# thegardening2_1.net
KiCad netlist of a schematic drawn in EAGLE
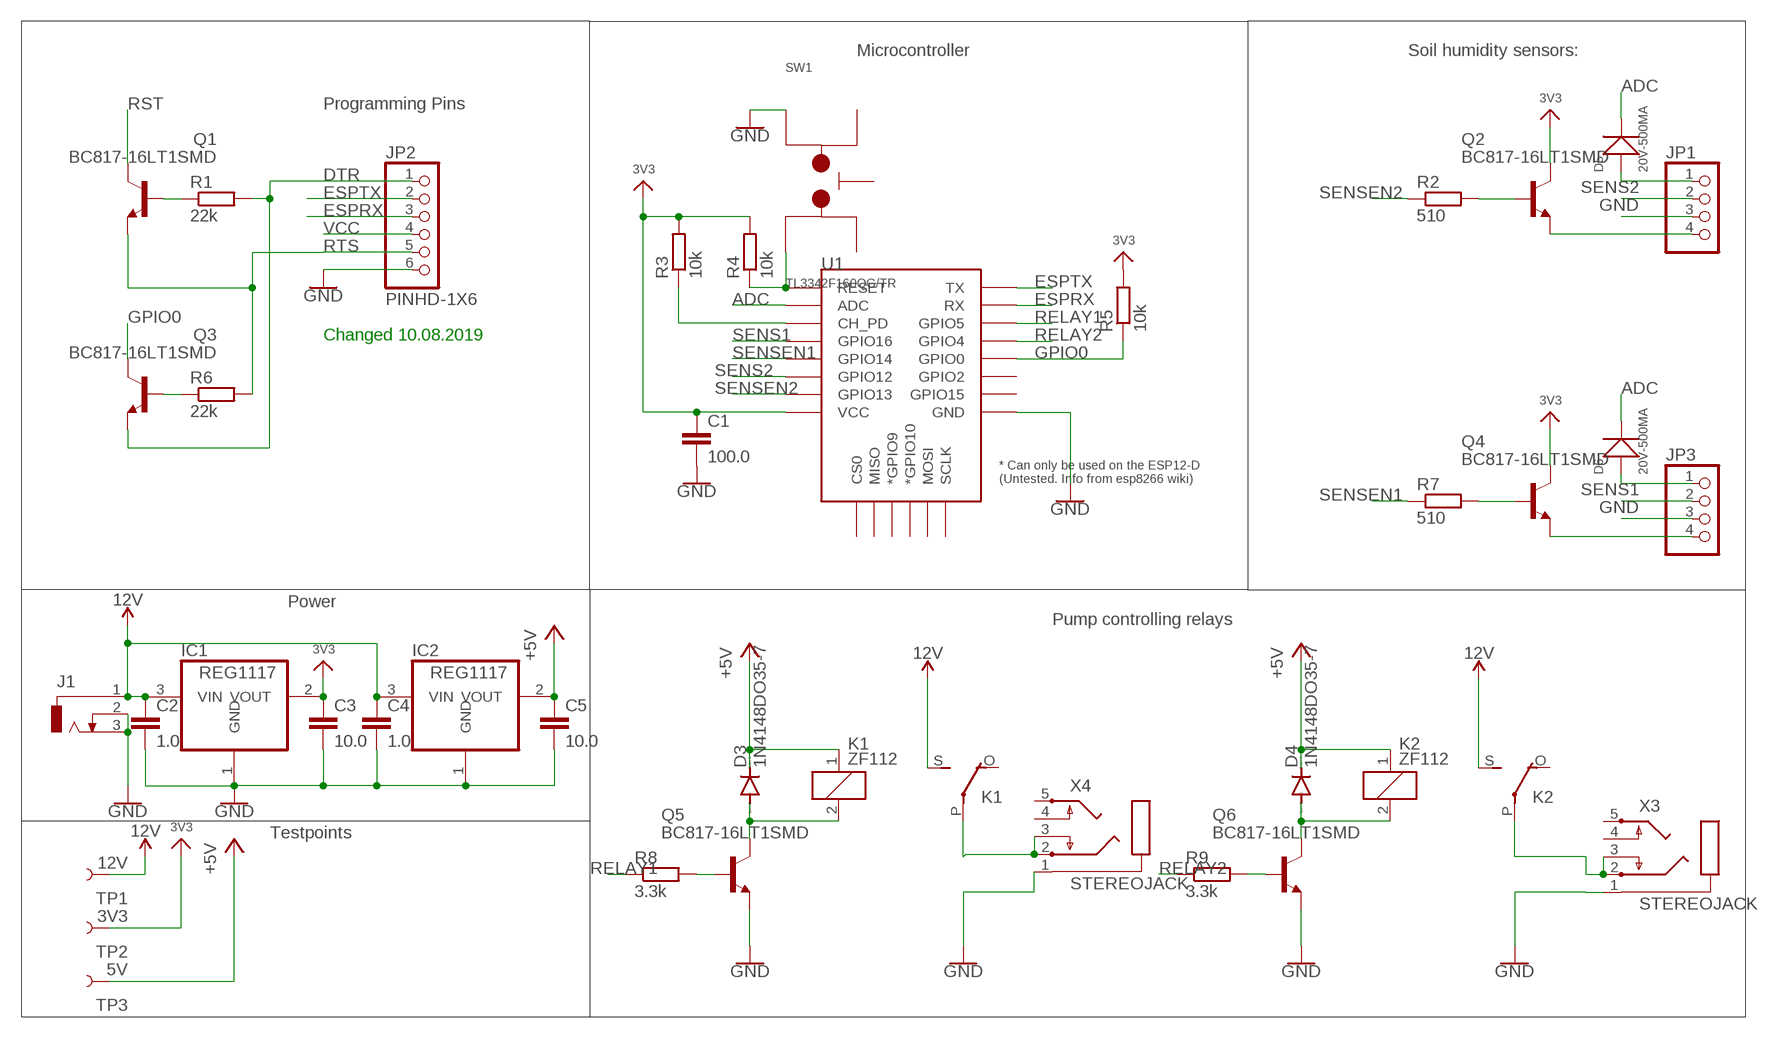
[diagram p0: schematic, sheet 1]

(export (version "E")
  (design (tool "Eeschema 10.0.6"))
  (components
    (comp (ref "C1")
      (value "100.0")
      (footprint "eagle-import:C0805")
      (libsource (lib "eagle-import") (part "C-EUC0805"))
    )
    (comp (ref "C2")
      (value "1.0")
      (footprint "eagle-import:C0805")
      (libsource (lib "eagle-import") (part "C-EUC0805"))
    )
    (comp (ref "C3")
      (value "10.0")
      (footprint "eagle-import:C0805")
      (libsource (lib "eagle-import") (part "C-EUC0805"))
    )
    (comp (ref "C4")
      (value "1.0")
      (footprint "eagle-import:C0805")
      (libsource (lib "eagle-import") (part "C-EUC0805"))
    )
    (comp (ref "C5")
      (value "10.0")
      (footprint "eagle-import:C0805")
      (libsource (lib "eagle-import") (part "C-EUC0805"))
    )
    (comp (ref "D3")
      (value "1N4148DO35-7")
      (footprint "eagle-import:DO35-7")
      (libsource (lib "eagle-import") (part "1N4148DO35-7"))
    )
    (comp (ref "D4")
      (value "1N4148DO35-7")
      (footprint "eagle-import:DO35-7")
      (libsource (lib "eagle-import") (part "1N4148DO35-7"))
    )
    (comp (ref "D5")
      (value "20V-500MA")
      (footprint "eagle-import:SOD-123")
      (fields (field (name "MPN") "SS0520-7-F"))
      (libsource (lib "eagle-import") (part "SMD-DIODE-SCHOTTKY-20V-500MA(SOD-123)"))
    )
    (comp (ref "D6")
      (value "20V-500MA")
      (footprint "eagle-import:SOD-123")
      (fields (field (name "MPN") "SS0520-7-F"))
      (libsource (lib "eagle-import") (part "SMD-DIODE-SCHOTTKY-20V-500MA(SOD-123)"))
    )
    (comp (ref "IC1")
      (value "REG1117")
      (footprint "eagle-import:SOT223")
      (libsource (lib "eagle-import") (part "REG1117"))
    )
    (comp (ref "IC2")
      (value "REG1117")
      (footprint "eagle-import:SOT223")
      (libsource (lib "eagle-import") (part "REG1117"))
    )
    (comp (ref "J1")
      (value "DCJ0303")
      (footprint "eagle-import:DCJ0303")
      (libsource (lib "eagle-import") (part "DCJ0303"))
    )
    (comp (ref "JP1")
      (value "PINHD-1X4")
      (footprint "eagle-import:1X04")
      (libsource (lib "eagle-import") (part "PINHD-1X4"))
    )
    (comp (ref "JP2")
      (value "PINHD-1X6")
      (footprint "eagle-import:1X06")
      (libsource (lib "eagle-import") (part "PINHD-1X6"))
    )
    (comp (ref "JP3")
      (value "PINHD-1X4")
      (footprint "eagle-import:1X04")
      (libsource (lib "eagle-import") (part "PINHD-1X4"))
    )
    (comp (ref "K1")
      (value "ZF112")
      (footprint "eagle-import:ZF112")
      (libsource (lib "eagle-import") (part "ZF112"))
    )
    (comp (ref "K2")
      (value "ZF112")
      (footprint "eagle-import:ZF112")
      (libsource (lib "eagle-import") (part "ZF112"))
    )
    (comp (ref "Q1")
      (value "BC817-16LT1SMD")
      (footprint "eagle-import:SOT23-BEC")
      (libsource (lib "eagle-import") (part "BC817SMD-16LT1"))
    )
    (comp (ref "Q2")
      (value "BC817-16LT1SMD")
      (footprint "eagle-import:SOT23-BEC")
      (libsource (lib "eagle-import") (part "BC817SMD-16LT1"))
    )
    (comp (ref "Q3")
      (value "BC817-16LT1SMD")
      (footprint "eagle-import:SOT23-BEC")
      (libsource (lib "eagle-import") (part "BC817SMD-16LT1"))
    )
    (comp (ref "Q4")
      (value "BC817-16LT1SMD")
      (footprint "eagle-import:SOT23-BEC")
      (libsource (lib "eagle-import") (part "BC817SMD-16LT1"))
    )
    (comp (ref "Q5")
      (value "BC817-16LT1SMD")
      (footprint "eagle-import:SOT23-BEC")
      (libsource (lib "eagle-import") (part "BC817SMD-16LT1"))
    )
    (comp (ref "Q6")
      (value "BC817-16LT1SMD")
      (footprint "eagle-import:SOT23-BEC")
      (libsource (lib "eagle-import") (part "BC817SMD-16LT1"))
    )
    (comp (ref "R1")
      (value "22k")
      (footprint "eagle-import:R0805")
      (libsource (lib "eagle-import") (part "R-EU_R0805"))
    )
    (comp (ref "R2")
      (value "510")
      (footprint "eagle-import:R0805")
      (libsource (lib "eagle-import") (part "R-EU_R0805"))
    )
    (comp (ref "R3")
      (value "10k")
      (footprint "eagle-import:R0805")
      (libsource (lib "eagle-import") (part "R-EU_R0805"))
    )
    (comp (ref "R4")
      (value "10k")
      (footprint "eagle-import:R0805")
      (libsource (lib "eagle-import") (part "R-EU_R0805"))
    )
    (comp (ref "R5")
      (value "10k")
      (footprint "eagle-import:R0805")
      (libsource (lib "eagle-import") (part "R-EU_R0805"))
    )
    (comp (ref "R6")
      (value "22k")
      (footprint "eagle-import:R0805")
      (libsource (lib "eagle-import") (part "R-EU_R0805"))
    )
    (comp (ref "R7")
      (value "510")
      (footprint "eagle-import:R0805")
      (libsource (lib "eagle-import") (part "R-EU_R0805"))
    )
    (comp (ref "R8")
      (value "3.3k")
      (footprint "eagle-import:R0805")
      (libsource (lib "eagle-import") (part "R-EU_R0805"))
    )
    (comp (ref "R9")
      (value "3.3k")
      (footprint "eagle-import:R0805")
      (libsource (lib "eagle-import") (part "R-EU_R0805"))
    )
    (comp (ref "SW1")
      (value "TL3342F160QG/TR")
      (footprint "eagle-import:TL3342F160QG_TR")
      (fields
        (field (name "DIGI_KEY_PART_NUMBER") "EG2531CT-ND")
        (field (name "MANUFACTURER") "E-Switch")
        (field (name "CREATED_BY") "PCBLayout.com")
      )
      (libsource (lib "eagle-import") (part "TL3342F160QG/TR"))
    )
    (comp (ref "TP1")
      (value "12V")
      (footprint "eagle-import:TP_15TH")
      (libsource (lib "eagle-import") (part "TEST-POINTTP_15TH_THRU"))
    )
    (comp (ref "TP2")
      (value "3V3")
      (footprint "eagle-import:TP_15TH")
      (libsource (lib "eagle-import") (part "TEST-POINTTP_15TH_THRU"))
    )
    (comp (ref "TP3")
      (value "5V")
      (footprint "eagle-import:TP_15TH")
      (libsource (lib "eagle-import") (part "TEST-POINTTP_15TH_THRU"))
    )
    (comp (ref "U1")
      (value "ESP12ESMD")
      (footprint "eagle-import:ESP12E-SMD")
      (libsource (lib "eagle-import") (part "ESP12ESMD"))
    )
    (comp (ref "X3")
      (value "STEREOJACK")
      (footprint "eagle-import:STX3100")
      (libsource (lib "eagle-import") (part "STEREOJACK"))
    )
    (comp (ref "X4")
      (value "STEREOJACK")
      (footprint "eagle-import:STX3100")
      (libsource (lib "eagle-import") (part "STEREOJACK"))
    )
  )
  (nets
    (net (code "1") (name "+5V") (class "Default")
      (node (ref "C5") (pin "1") (pinfunction "1_1") (pintype "passive"))
      (node (ref "D3") (pin "C") (pinfunction "C_C") (pintype "passive"))
      (node (ref "D4") (pin "C") (pinfunction "C_C") (pintype "passive"))
      (node (ref "IC2") (pin "2") (pinfunction "VOUT_2") (pintype "output"))
      (node (ref "K1") (pin "1") (pinfunction "1_1") (pintype "passive"))
      (node (ref "K2") (pin "1") (pinfunction "1_1") (pintype "passive"))
      (node (ref "TP3") (pin "P$1") (pinfunction "1_P$1") (pintype "bidirectional"))
    )
    (net (code "2") (name "/ADC") (class "Default")
      (node (ref "D5") (pin "-") (pinfunction "-_-") (pintype "passive"))
      (node (ref "D6") (pin "-") (pinfunction "-_-") (pintype "passive"))
      (node (ref "U1") (pin "ADC") (pinfunction "ADC_ADC") (pintype "bidirectional"))
    )
    (net (code "3") (name "/DTR") (class "Default")
      (node (ref "JP2") (pin "1") (pinfunction "1_1") (pintype "passive"))
      (node (ref "Q3") (pin "E") (pinfunction "E_E") (pintype "passive"))
      (node (ref "R1") (pin "2") (pinfunction "2_2") (pintype "passive"))
    )
    (net (code "4") (name "/ESPRX") (class "Default")
      (node (ref "JP2") (pin "3") (pinfunction "3_3") (pintype "passive"))
      (node (ref "U1") (pin "RXD0") (pinfunction "RX_RXD0") (pintype "bidirectional"))
    )
    (net (code "5") (name "/ESPTX") (class "Default")
      (node (ref "JP2") (pin "2") (pinfunction "2_2") (pintype "passive"))
      (node (ref "U1") (pin "TXD0") (pinfunction "TX_TXD0") (pintype "bidirectional"))
    )
    (net (code "6") (name "/GPIO0") (class "Default")
      (node (ref "Q3") (pin "C") (pinfunction "C_C") (pintype "passive"))
      (node (ref "R5") (pin "1") (pinfunction "1_1") (pintype "passive"))
      (node (ref "U1") (pin "GPIO0") (pinfunction "GPIO0_GPIO0") (pintype "bidirectional"))
    )
    (net (code "7") (name "/RELAY1") (class "Default")
      (node (ref "R8") (pin "1") (pinfunction "1_1") (pintype "passive"))
      (node (ref "U1") (pin "GPIO5") (pinfunction "GPIO5_GPIO5") (pintype "bidirectional"))
    )
    (net (code "8") (name "/RELAY2") (class "Default")
      (node (ref "R9") (pin "1") (pinfunction "1_1") (pintype "passive"))
      (node (ref "U1") (pin "GPIO4") (pinfunction "GPIO4_GPIO4") (pintype "bidirectional"))
    )
    (net (code "9") (name "/RST") (class "Default")
      (node (ref "Q1") (pin "C") (pinfunction "C_C") (pintype "passive"))
      (node (ref "R4") (pin "1") (pinfunction "1_1") (pintype "passive"))
      (node (ref "SW1") (pin "1") (pinfunction "1_1") (pintype "passive"))
      (node (ref "U1") (pin "RESET") (pinfunction "RESET_RESET") (pintype "bidirectional"))
    )
    (net (code "10") (name "/RTS") (class "Default")
      (node (ref "JP2") (pin "5") (pinfunction "5_5") (pintype "passive"))
      (node (ref "Q1") (pin "E") (pinfunction "E_E") (pintype "passive"))
      (node (ref "R6") (pin "2") (pinfunction "2_2") (pintype "passive"))
    )
    (net (code "11") (name "/SENS1") (class "Default")
      (node (ref "JP3") (pin "2") (pinfunction "2_2") (pintype "passive"))
      (node (ref "U1") (pin "GPIO16") (pinfunction "GPIO16_GPIO16") (pintype "bidirectional"))
    )
    (net (code "12") (name "/SENS2") (class "Default")
      (node (ref "JP1") (pin "2") (pinfunction "2_2") (pintype "passive"))
      (node (ref "U1") (pin "GPIO12") (pinfunction "GPIO12_GPIO12") (pintype "bidirectional"))
    )
    (net (code "13") (name "/SENSEN1") (class "Default")
      (node (ref "R7") (pin "1") (pinfunction "1_1") (pintype "passive"))
      (node (ref "U1") (pin "GPIO14") (pinfunction "GPIO14_GPIO14") (pintype "bidirectional"))
    )
    (net (code "14") (name "/SENSEN2") (class "Default")
      (node (ref "R2") (pin "1") (pinfunction "1_1") (pintype "passive"))
      (node (ref "U1") (pin "GPIO13") (pinfunction "GPIO13_GPIO13") (pintype "bidirectional"))
    )
    (net (code "15") (name "3V3") (class "Default")
      (node (ref "C1") (pin "1") (pinfunction "1_1") (pintype "passive"))
      (node (ref "C3") (pin "1") (pinfunction "1_1") (pintype "passive"))
      (node (ref "IC1") (pin "2") (pinfunction "VOUT_2") (pintype "output"))
      (node (ref "JP2") (pin "4") (pinfunction "4_4") (pintype "passive"))
      (node (ref "Q2") (pin "C") (pinfunction "C_C") (pintype "passive"))
      (node (ref "Q4") (pin "C") (pinfunction "C_C") (pintype "passive"))
      (node (ref "R3") (pin "2") (pinfunction "2_2") (pintype "passive"))
      (node (ref "R4") (pin "2") (pinfunction "2_2") (pintype "passive"))
      (node (ref "R5") (pin "2") (pinfunction "2_2") (pintype "passive"))
      (node (ref "TP2") (pin "P$1") (pinfunction "1_P$1") (pintype "bidirectional"))
      (node (ref "U1") (pin "VCC") (pinfunction "VCC_VCC") (pintype "bidirectional"))
    )
    (net (code "16") (name "12V") (class "Default")
      (node (ref "C2") (pin "1") (pinfunction "1_1") (pintype "passive"))
      (node (ref "C4") (pin "1") (pinfunction "1_1") (pintype "passive"))
      (node (ref "IC1") (pin "3") (pinfunction "VIN_3") (pintype "input"))
      (node (ref "IC2") (pin "3") (pinfunction "VIN_3") (pintype "input"))
      (node (ref "J1") (pin "1") (pinfunction "1_1") (pintype "passive"))
      (node (ref "K1") (pin "S") (pinfunction "S_S") (pintype "passive"))
      (node (ref "K2") (pin "S") (pinfunction "S_S") (pintype "passive"))
      (node (ref "TP1") (pin "P$1") (pinfunction "1_P$1") (pintype "bidirectional"))
    )
    (net (code "17") (name "GND") (class "Default")
      (node (ref "C1") (pin "2") (pinfunction "2_2") (pintype "passive"))
      (node (ref "C2") (pin "2") (pinfunction "2_2") (pintype "passive"))
      (node (ref "C3") (pin "2") (pinfunction "2_2") (pintype "passive"))
      (node (ref "C4") (pin "2") (pinfunction "2_2") (pintype "passive"))
      (node (ref "C5") (pin "2") (pinfunction "2_2") (pintype "passive"))
      (node (ref "IC1") (pin "1") (pinfunction "GND_1") (pintype "power_in"))
      (node (ref "IC2") (pin "1") (pinfunction "GND_1") (pintype "power_in"))
      (node (ref "J1") (pin "2") (pinfunction "2_2") (pintype "passive"))
      (node (ref "J1") (pin "3") (pinfunction "3_3") (pintype "passive"))
      (node (ref "JP1") (pin "3") (pinfunction "3_3") (pintype "passive"))
      (node (ref "JP2") (pin "6") (pinfunction "6_6") (pintype "passive"))
      (node (ref "JP3") (pin "3") (pinfunction "3_3") (pintype "passive"))
      (node (ref "Q5") (pin "E") (pinfunction "E_E") (pintype "passive"))
      (node (ref "Q6") (pin "E") (pinfunction "E_E") (pintype "passive"))
      (node (ref "SW1") (pin "3") (pinfunction "3_3") (pintype "passive"))
      (node (ref "U1") (pin "GND") (pinfunction "GND_GND") (pintype "bidirectional"))
      (node (ref "X3") (pin "1") (pinfunction "1_1") (pintype "passive"))
      (node (ref "X4") (pin "1") (pinfunction "1_1") (pintype "passive"))
    )
    (net (code "18") (name "Net-(D3-PadA)") (class "Default")
      (node (ref "D3") (pin "A") (pinfunction "A_A") (pintype "passive"))
      (node (ref "K1") (pin "2") (pinfunction "2_2") (pintype "passive"))
      (node (ref "Q5") (pin "C") (pinfunction "C_C") (pintype "passive"))
    )
    (net (code "19") (name "Net-(D4-PadA)") (class "Default")
      (node (ref "D4") (pin "A") (pinfunction "A_A") (pintype "passive"))
      (node (ref "K2") (pin "2") (pinfunction "2_2") (pintype "passive"))
      (node (ref "Q6") (pin "C") (pinfunction "C_C") (pintype "passive"))
    )
    (net (code "20") (name "Net-(D5-Pad+)") (class "Default")
      (node (ref "D5") (pin "+") (pinfunction "+_+") (pintype "passive"))
      (node (ref "JP1") (pin "1") (pinfunction "1_1") (pintype "passive"))
    )
    (net (code "21") (name "Net-(D6-Pad+)") (class "Default")
      (node (ref "D6") (pin "+") (pinfunction "+_+") (pintype "passive"))
      (node (ref "JP3") (pin "1") (pinfunction "1_1") (pintype "passive"))
    )
    (net (code "22") (name "Net-(JP1-Pad4)") (class "Default")
      (node (ref "JP1") (pin "4") (pinfunction "4_4") (pintype "passive"))
      (node (ref "Q2") (pin "E") (pinfunction "E_E") (pintype "passive"))
    )
    (net (code "23") (name "Net-(JP3-Pad4)") (class "Default")
      (node (ref "JP3") (pin "4") (pinfunction "4_4") (pintype "passive"))
      (node (ref "Q4") (pin "E") (pinfunction "E_E") (pintype "passive"))
    )
    (net (code "24") (name "Net-(K1-PadP)") (class "Default")
      (node (ref "K1") (pin "P") (pinfunction "P_P") (pintype "passive"))
      (node (ref "X4") (pin "2") (pinfunction "2_2") (pintype "passive"))
      (node (ref "X4") (pin "3") (pinfunction "3_3") (pintype "passive"))
    )
    (net (code "25") (name "Net-(K2-PadP)") (class "Default")
      (node (ref "K2") (pin "P") (pinfunction "P_P") (pintype "passive"))
      (node (ref "X3") (pin "2") (pinfunction "2_2") (pintype "passive"))
      (node (ref "X3") (pin "3") (pinfunction "3_3") (pintype "passive"))
    )
    (net (code "26") (name "Net-(Q1-PadB)") (class "Default")
      (node (ref "Q1") (pin "B") (pinfunction "B_B") (pintype "passive"))
      (node (ref "R1") (pin "1") (pinfunction "1_1") (pintype "passive"))
    )
    (net (code "27") (name "Net-(Q2-PadB)") (class "Default")
      (node (ref "Q2") (pin "B") (pinfunction "B_B") (pintype "passive"))
      (node (ref "R2") (pin "2") (pinfunction "2_2") (pintype "passive"))
    )
    (net (code "28") (name "Net-(Q3-PadB)") (class "Default")
      (node (ref "Q3") (pin "B") (pinfunction "B_B") (pintype "passive"))
      (node (ref "R6") (pin "1") (pinfunction "1_1") (pintype "passive"))
    )
    (net (code "29") (name "Net-(Q4-PadB)") (class "Default")
      (node (ref "Q4") (pin "B") (pinfunction "B_B") (pintype "passive"))
      (node (ref "R7") (pin "2") (pinfunction "2_2") (pintype "passive"))
    )
    (net (code "30") (name "Net-(Q5-PadB)") (class "Default")
      (node (ref "Q5") (pin "B") (pinfunction "B_B") (pintype "passive"))
      (node (ref "R8") (pin "2") (pinfunction "2_2") (pintype "passive"))
    )
    (net (code "31") (name "Net-(Q6-PadB)") (class "Default")
      (node (ref "Q6") (pin "B") (pinfunction "B_B") (pintype "passive"))
      (node (ref "R9") (pin "2") (pinfunction "2_2") (pintype "passive"))
    )
    (net (code "32") (name "Net-(R3-Pad1)") (class "Default")
      (node (ref "R3") (pin "1") (pinfunction "1_1") (pintype "passive"))
      (node (ref "U1") (pin "CH_PD") (pinfunction "CH_PD_CH_PD") (pintype "bidirectional"))
    )
    (net (code "33") (name "unconnected-(K1-PadO)") (class "Default")
      (node (ref "K1") (pin "O") (pinfunction "O_O") (pintype "passive"))
    )
    (net (code "34") (name "unconnected-(K2-PadO)") (class "Default")
      (node (ref "K2") (pin "O") (pinfunction "O_O") (pintype "passive"))
    )
    (net (code "35") (name "unconnected-(SW1-Pad2)") (class "Default")
      (node (ref "SW1") (pin "2") (pinfunction "2_2") (pintype "passive"))
    )
    (net (code "36") (name "unconnected-(SW1-Pad4)") (class "Default")
      (node (ref "SW1") (pin "4") (pinfunction "4_4") (pintype "passive"))
    )
    (net (code "37") (name "unconnected-(U1-*GPIO9-PadGPIO9)") (class "Default")
      (node (ref "U1") (pin "GPIO9") (pinfunction "*GPIO9_GPIO9") (pintype "bidirectional"))
    )
    (net (code "38") (name "unconnected-(U1-*GPIO10-PadGPIO10)") (class "Default")
      (node (ref "U1") (pin "GPIO10") (pinfunction "*GPIO10_GPIO10") (pintype "bidirectional"))
    )
    (net (code "39") (name "unconnected-(U1-PadCS0)") (class "Default")
      (node (ref "U1") (pin "CS0") (pinfunction "CS0_CS0") (pintype "bidirectional"))
    )
    (net (code "40") (name "unconnected-(U1-PadGPIO2)") (class "Default")
      (node (ref "U1") (pin "GPIO2") (pinfunction "GPIO2_GPIO2") (pintype "bidirectional"))
    )
    (net (code "41") (name "unconnected-(U1-PadGPIO15)") (class "Default")
      (node (ref "U1") (pin "GPIO15") (pinfunction "GPIO15_GPIO15") (pintype "bidirectional"))
    )
    (net (code "42") (name "unconnected-(U1-PadMISO)") (class "Default")
      (node (ref "U1") (pin "MISO") (pinfunction "MISO_MISO") (pintype "bidirectional"))
    )
    (net (code "43") (name "unconnected-(U1-PadMOSI)") (class "Default")
      (node (ref "U1") (pin "MOSI") (pinfunction "MOSI_MOSI") (pintype "bidirectional"))
    )
    (net (code "44") (name "unconnected-(U1-PadSCLK)") (class "Default")
      (node (ref "U1") (pin "SCLK") (pinfunction "SCLK_SCLK") (pintype "bidirectional"))
    )
    (net (code "45") (name "unconnected-(X3-Pad4)") (class "Default")
      (node (ref "X3") (pin "4") (pinfunction "4_4") (pintype "passive"))
    )
    (net (code "46") (name "unconnected-(X3-Pad5)") (class "Default")
      (node (ref "X3") (pin "5") (pinfunction "5_5") (pintype "passive"))
    )
    (net (code "47") (name "unconnected-(X4-Pad4)") (class "Default")
      (node (ref "X4") (pin "4") (pinfunction "4_4") (pintype "passive"))
    )
    (net (code "48") (name "unconnected-(X4-Pad5)") (class "Default")
      (node (ref "X4") (pin "5") (pinfunction "5_5") (pintype "passive"))
    )
  )
)
